# Sche.net
KiCad netlist of a schematic drawn in Altium Designer
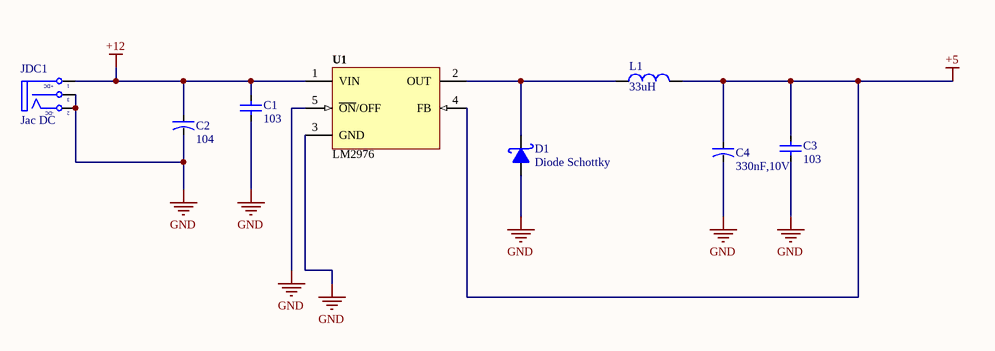
[diagram p0: Sche.SchDoc]

(export (version "E")
  (design (tool "Eeschema 10.0.6"))
  (components
    (comp (ref "C1")
      (value "103")
      (footprint "CAP_0402")
      (description "Capacitor")
      (fields (field (name "PUBLISHER") "Altium Limited"))
      (libsource (lib "My-Library") (part "CapSMD"))
    )
    (comp (ref "C2")
      (value "104")
      (footprint "CA-ALU-2.54")
      (description "Capacitor (Semiconductor SIM Model)")
      (fields (field (name "PUBLISHER") "Altium Limited"))
      (libsource (lib "My-Library") (part "CAP-ALU-DIP"))
    )
    (comp (ref "C3")
      (value "103")
      (footprint "CAP_0402")
      (description "Capacitor")
      (fields (field (name "PUBLISHER") "Altium Limited"))
      (libsource (lib "My-Library") (part "CapSMD"))
    )
    (comp (ref "C4")
      (value "330nF,10V")
      (footprint "CA-ALU-2.54")
      (description "Capacitor (Semiconductor SIM Model)")
      (fields (field (name "PUBLISHER") "Altium Limited"))
      (libsource (lib "My-Library") (part "CAP-ALU-DIP"))
    )
    (comp (ref "D1")
      (value "Diode Schottky")
      (footprint "DIO-3A")
      (description "Generic Diode Schottky")
      (libsource (lib "My-Library") (part "Diode Schottky"))
    )
    (comp (ref "JDC1")
      (value "Jac DC")
      (footprint "DC-IN")
      (description "Jac DC input")
      (libsource (lib "My-Library") (part "DCIN"))
    )
    (comp (ref "L1")
      (value "33uH")
      (footprint "L-SMD-M-12x10")
      (description "Inductor")
      (libsource (lib "My-Library") (part "Inductor"))
    )
    (comp (ref "U1") (value "LM2976") (footprint "TO263-5") (libsource (lib "My-Library") (part "LM2596")))
  )
  (nets
    (net (code "1") (name "+5") (class "Default")
      (node (ref "C3") (pin "1") (pinfunction "1_1") (pintype "passive"))
      (node (ref "C4") (pin "1") (pinfunction "1_1") (pintype "passive"))
      (node (ref "L1") (pin "2") (pinfunction "2_2") (pintype "passive"))
      (node (ref "U1") (pin "4") (pinfunction "FB_4") (pintype "input"))
    )
    (net (code "2") (name "+12") (class "Default")
      (node (ref "C1") (pin "2") (pinfunction "2_2") (pintype "passive"))
      (node (ref "C2") (pin "1") (pinfunction "1_1") (pintype "passive"))
      (node (ref "JDC1") (pin "1") (pinfunction "T_1") (pintype "passive"))
      (node (ref "U1") (pin "1") (pinfunction "VIN_1") (pintype "power_in"))
    )
    (net (code "3") (name "GND") (class "Default")
      (node (ref "C1") (pin "1") (pinfunction "1_1") (pintype "passive"))
      (node (ref "C2") (pin "2") (pinfunction "2_2") (pintype "passive"))
      (node (ref "C3") (pin "2") (pinfunction "2_2") (pintype "passive"))
      (node (ref "C4") (pin "2") (pinfunction "2_2") (pintype "passive"))
      (node (ref "D1") (pin "1") (pinfunction "A_1") (pintype "passive"))
      (node (ref "JDC1") (pin "2") (pinfunction "TN_2") (pintype "passive"))
      (node (ref "JDC1") (pin "3") (pinfunction "S_3") (pintype "power_in"))
      (node (ref "U1") (pin "3") (pinfunction "GND_3") (pintype "power_in"))
      (node (ref "U1") (pin "5") (pinfunction "~{ON}/OFF_5") (pintype "input"))
    )
    (net (code "4") (name "Net-(D1-K)") (class "Default")
      (node (ref "D1") (pin "2") (pinfunction "K_2") (pintype "passive"))
      (node (ref "L1") (pin "1") (pinfunction "1_1") (pintype "passive"))
      (node (ref "U1") (pin "2") (pinfunction "OUT_2") (pintype "power_in"))
    )
  )
)
